# power_suppliers.net
KiCad netlist of a schematic drawn in Altium Designer
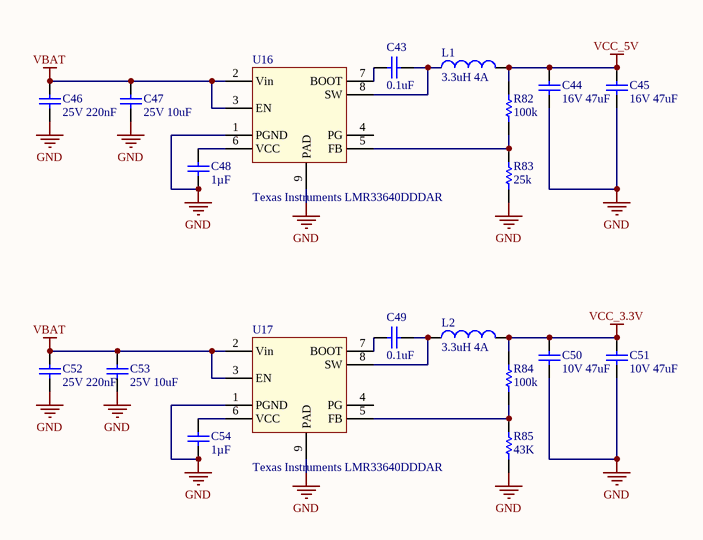
[diagram p0: power_suppliers.SchDoc]

(export (version "E")
  (design (tool "Eeschema 10.0.6"))
  (components
    (comp (ref "C43")
      (value "0.1uF")
      (footprint "CAPC1608X90X35LL15T15")
      (description "Cap Ceramic 0.1uF 16V X7R 10% SMD 0603 125C Paper T/R")
      (fields (field (name "MANUFACTURER PART NUMBER") "0603YC104K4T2A"))
      (libsource (lib "CommunityVault") (part "CMP-175023-2"))
    )
    (comp (ref "C44")
      (value "16V 47uF")
      (footprint "PCB-h26gble9h939l4c191wl-1")
      (description "1210 47 uF 10 V ±10% Tolerance X5R SMT Multilayer Ceramic Capacitor")
      (fields (field (name "MANUFACTURER PART NUMBER") "GRM32ER61A476KE20L"))
      (libsource (lib "CommunityVault") (part "SYM-cdd204dbeb8b1215-1"))
    )
    (comp (ref "C45")
      (value "16V 47uF")
      (footprint "PCB-h26gble9h939l4c191wl-1")
      (description "1210 47 uF 10 V ±10% Tolerance X5R SMT Multilayer Ceramic Capacitor")
      (fields (field (name "MANUFACTURER PART NUMBER") "GRM32ER61A476KE20L"))
      (libsource (lib "CommunityVault") (part "SYM-cdd204dbeb8b1215-1"))
    )
    (comp (ref "C46")
      (value "25V 220nF")
      (footprint "CAPC1608X90X35LL15T15")
      (description "CAP CER 0.22UF 25V 10% X5R 0603")
      (fields (field (name "MANUFACTURER PART NUMBER") "06033D224KAT2A"))
      (libsource (lib "CommunityVault") (part "CMP-126800-2"))
    )
    (comp (ref "C47")
      (value "25V 10uF")
      (footprint "CAPC3225X279X50NL20T25")
      (description "CAP CER 10UF 25V 10% X5R 1210")
      (fields (field (name "MANUFACTURER PART NUMBER") "12103D106KAT2A"))
      (libsource (lib "CommunityVault") (part "CMP-127194-2"))
    )
    (comp (ref "C48")
      (value "1µF")
      (footprint "CAPC1608X90X35ML15T15")
      (description "0603 1 uF 16 V ±10 % Tolerance X5R SMT Multilayer Ceramic Capacitor")
      (libsource (lib "CommunityVault") (part "CAP-NP-2"))
    )
    (comp (ref "C49")
      (value "0.1uF")
      (footprint "CAPC1608X90X35LL15T15")
      (description "Cap Ceramic 0.1uF 16V X7R 10% SMD 0603 125C Paper T/R")
      (fields (field (name "MANUFACTURER PART NUMBER") "0603YC104K4T2A"))
      (libsource (lib "CommunityVault") (part "CMP-175023-2"))
    )
    (comp (ref "C50")
      (value "10V 47uF")
      (footprint "PCB-h26gble9h939l4c191wl-1")
      (description "1210 47 uF 10 V ±10% Tolerance X5R SMT Multilayer Ceramic Capacitor")
      (fields (field (name "MANUFACTURER PART NUMBER") "GRM32ER61A476KE20L"))
      (libsource (lib "CommunityVault") (part "SYM-cdd204dbeb8b1215-1"))
    )
    (comp (ref "C51")
      (value "10V 47uF")
      (footprint "PCB-h26gble9h939l4c191wl-1")
      (description "1210 47 uF 10 V ±10% Tolerance X5R SMT Multilayer Ceramic Capacitor")
      (fields (field (name "MANUFACTURER PART NUMBER") "GRM32ER61A476KE20L"))
      (libsource (lib "CommunityVault") (part "SYM-cdd204dbeb8b1215-1"))
    )
    (comp (ref "C52")
      (value "25V 220nF")
      (footprint "CAPC1608X90X35LL15T15")
      (description "CAP CER 0.22UF 25V 10% X5R 0603")
      (fields (field (name "MANUFACTURER PART NUMBER") "06033D224KAT2A"))
      (libsource (lib "CommunityVault") (part "CMP-126800-2"))
    )
    (comp (ref "C53")
      (value "25V 10uF")
      (footprint "CAPC3225X279X50NL20T25")
      (description "CAP CER 10UF 25V 10% X5R 1210")
      (fields (field (name "MANUFACTURER PART NUMBER") "12103D106KAT2A"))
      (libsource (lib "CommunityVault") (part "CMP-127194-2"))
    )
    (comp (ref "C54")
      (value "1µF")
      (footprint "CAPC1608X90X35ML15T15")
      (description "0603 1 uF 16 V ±10 % Tolerance X5R SMT Multilayer Ceramic Capacitor")
      (libsource (lib "CommunityVault") (part "CAP-NP-2"))
    )
    (comp (ref "L1")
      (value "3.3uH 4A")
      (footprint "PCB-nnnro8dea2m4q1g7ugdq-1")
      (description "Power inductor, shielded, 10/20/30% tol, SMT, RoHS")
      (fields (field (name "MANUFACTURER PART NUMBER") "MSS1048-683MLC"))
      (libsource (lib "CommunityVault") (part "CMP-d4431d2f1dc30b84-1"))
    )
    (comp (ref "L2")
      (value "3.3uH 4A")
      (footprint "PCB-nnnro8dea2m4q1g7ugdq-1")
      (description "Power inductor, shielded, 10/20/30% tol, SMT, RoHS")
      (fields (field (name "MANUFACTURER PART NUMBER") "MSS1048-683MLC"))
      (libsource (lib "CommunityVault") (part "CMP-d4431d2f1dc30b84-1"))
    )
    (comp (ref "R82")
      (value "100k")
      (footprint "RESC1608X55X30LL15T15")
      (description "Res General Purpose Thick Film 0603 100k Ohm 1% 1/10W ±100ppm/°C Molded Paper T/R")
      (libsource (lib "CommunityVault") (part "RES-2"))
    )
    (comp (ref "R83")
      (value "25k")
      (footprint "RESC1609X50X30LL10T20")
      (description "RES SMD 25.5K OHM 1% 1/10W 0603")
      (fields (field (name "MANUFACTURER PART NUMBER") "CRCW060325K5FKEA"))
      (libsource (lib "CommunityVault") (part "RES-2"))
    )
    (comp (ref "R84")
      (value "100k")
      (footprint "RESC1608X55X30LL15T15")
      (description "Res General Purpose Thick Film 0603 100k Ohm 1% 1/10W ±100ppm/°C Molded Paper T/R")
      (libsource (lib "CommunityVault") (part "RES-2"))
    )
    (comp (ref "R85")
      (value "43K")
      (footprint "RESC1608X55X30LL15T15")
      (description "Thick Film Resistors - SMD 0603 43Kohms 5% Tol")
      (fields (field (name "MANUFACTURER PART NUMBER") "ERJ-3GEYJ433V"))
      (libsource (lib "CommunityVault") (part "CMP-3653524-2"))
    )
    (comp (ref "U16")
      (value "Texas Instruments LMR33640DDDAR")
      (footprint "PCB-6od3ifqvrl04n4lmrw41-1")
      (description "SIMPLE SWITCHER Synchronous Step-Down Converter 3.8V to 36V Input 4A 8-Pin SO PowerPAD T/R")
      (libsource (lib "CommunityVault") (part "SYM-bb02745c510e64c5-1"))
    )
    (comp (ref "U17")
      (value "Texas Instruments LMR33640DDDAR")
      (footprint "PCB-6od3ifqvrl04n4lmrw41-1")
      (description "SIMPLE SWITCHER Synchronous Step-Down Converter 3.8V to 36V Input 4A 8-Pin SO PowerPAD T/R")
      (libsource (lib "CommunityVault") (part "SYM-bb02745c510e64c5-1"))
    )
  )
  (nets
    (net (code "1") (name "GND") (class "Default")
      (node (ref "C44") (pin "2") (pinfunction "2_2") (pintype "passive"))
      (node (ref "C45") (pin "2") (pinfunction "2_2") (pintype "passive"))
      (node (ref "C46") (pin "1") (pinfunction "1_1") (pintype "passive"))
      (node (ref "C47") (pin "1") (pinfunction "1_1") (pintype "passive"))
      (node (ref "C48") (pin "2") (pinfunction "2_2") (pintype "passive"))
      (node (ref "C50") (pin "2") (pinfunction "2_2") (pintype "passive"))
      (node (ref "C51") (pin "2") (pinfunction "2_2") (pintype "passive"))
      (node (ref "C52") (pin "1") (pinfunction "1_1") (pintype "passive"))
      (node (ref "C53") (pin "1") (pinfunction "1_1") (pintype "passive"))
      (node (ref "C54") (pin "2") (pinfunction "2_2") (pintype "passive"))
      (node (ref "R83") (pin "1") (pinfunction "1_1") (pintype "passive"))
      (node (ref "R85") (pin "1") (pinfunction "1_1") (pintype "passive"))
      (node (ref "U16") (pin "1") (pinfunction "PGND_1") (pintype "passive"))
      (node (ref "U16") (pin "9") (pinfunction "PAD_9") (pintype "passive"))
      (node (ref "U17") (pin "1") (pinfunction "PGND_1") (pintype "passive"))
      (node (ref "U17") (pin "9") (pinfunction "PAD_9") (pintype "passive"))
    )
    (net (code "2") (name "Net-(U16-BOOT)") (class "Default")
      (node (ref "C43") (pin "1") (pinfunction "1_1") (pintype "passive"))
      (node (ref "U16") (pin "7") (pinfunction "BOOT_7") (pintype "passive"))
    )
    (net (code "3") (name "Net-(U16-FB)") (class "Default")
      (node (ref "R82") (pin "1") (pinfunction "1_1") (pintype "passive"))
      (node (ref "R83") (pin "2") (pinfunction "2_2") (pintype "passive"))
      (node (ref "U16") (pin "5") (pinfunction "FB_5") (pintype "passive"))
    )
    (net (code "4") (name "Net-(U16-SW)") (class "Default")
      (node (ref "C43") (pin "2") (pinfunction "2_2") (pintype "passive"))
      (node (ref "L1") (pin "1") (pinfunction "1_1") (pintype "passive"))
      (node (ref "U16") (pin "8") (pinfunction "SW_8") (pintype "passive"))
    )
    (net (code "5") (name "Net-(U16-VCC)") (class "Default")
      (node (ref "C48") (pin "1") (pinfunction "1_1") (pintype "passive"))
      (node (ref "U16") (pin "6") (pinfunction "VCC_6") (pintype "passive"))
    )
    (net (code "6") (name "Net-(U17-BOOT)") (class "Default")
      (node (ref "C49") (pin "1") (pinfunction "1_1") (pintype "passive"))
      (node (ref "U17") (pin "7") (pinfunction "BOOT_7") (pintype "passive"))
    )
    (net (code "7") (name "Net-(U17-FB)") (class "Default")
      (node (ref "R84") (pin "1") (pinfunction "1_1") (pintype "passive"))
      (node (ref "R85") (pin "2") (pinfunction "2_2") (pintype "passive"))
      (node (ref "U17") (pin "5") (pinfunction "FB_5") (pintype "passive"))
    )
    (net (code "8") (name "Net-(U17-SW)") (class "Default")
      (node (ref "C49") (pin "2") (pinfunction "2_2") (pintype "passive"))
      (node (ref "L2") (pin "1") (pinfunction "1_1") (pintype "passive"))
      (node (ref "U17") (pin "8") (pinfunction "SW_8") (pintype "passive"))
    )
    (net (code "9") (name "Net-(U17-VCC)") (class "Default")
      (node (ref "C54") (pin "1") (pinfunction "1_1") (pintype "passive"))
      (node (ref "U17") (pin "6") (pinfunction "VCC_6") (pintype "passive"))
    )
    (net (code "10") (name "VBAT") (class "Default")
      (node (ref "C46") (pin "2") (pinfunction "2_2") (pintype "passive"))
      (node (ref "C47") (pin "2") (pinfunction "2_2") (pintype "passive"))
      (node (ref "C52") (pin "2") (pinfunction "2_2") (pintype "passive"))
      (node (ref "C53") (pin "2") (pinfunction "2_2") (pintype "passive"))
      (node (ref "U16") (pin "2") (pinfunction "Vin_2") (pintype "passive"))
      (node (ref "U16") (pin "3") (pinfunction "EN_3") (pintype "passive"))
      (node (ref "U17") (pin "2") (pinfunction "Vin_2") (pintype "passive"))
      (node (ref "U17") (pin "3") (pinfunction "EN_3") (pintype "passive"))
    )
    (net (code "11") (name "VCC_3.3V") (class "Default")
      (node (ref "C50") (pin "1") (pinfunction "1_1") (pintype "passive"))
      (node (ref "C51") (pin "1") (pinfunction "1_1") (pintype "passive"))
      (node (ref "L2") (pin "2") (pinfunction "2_2") (pintype "passive"))
      (node (ref "R84") (pin "2") (pinfunction "2_2") (pintype "passive"))
    )
    (net (code "12") (name "VCC_5V") (class "Default")
      (node (ref "C44") (pin "1") (pinfunction "1_1") (pintype "passive"))
      (node (ref "C45") (pin "1") (pinfunction "1_1") (pintype "passive"))
      (node (ref "L1") (pin "2") (pinfunction "2_2") (pintype "passive"))
      (node (ref "R82") (pin "2") (pinfunction "2_2") (pintype "passive"))
    )
    (net (code "13") (name "unconnected-(U16-PG-Pad4)") (class "Default")
      (node (ref "U16") (pin "4") (pinfunction "PG_4") (pintype "passive"))
    )
    (net (code "14") (name "unconnected-(U17-PG-Pad4)") (class "Default")
      (node (ref "U17") (pin "4") (pinfunction "PG_4") (pintype "passive"))
    )
  )
)
